# INTERFACE.net
KiCad netlist of a schematic drawn in Altium Designer
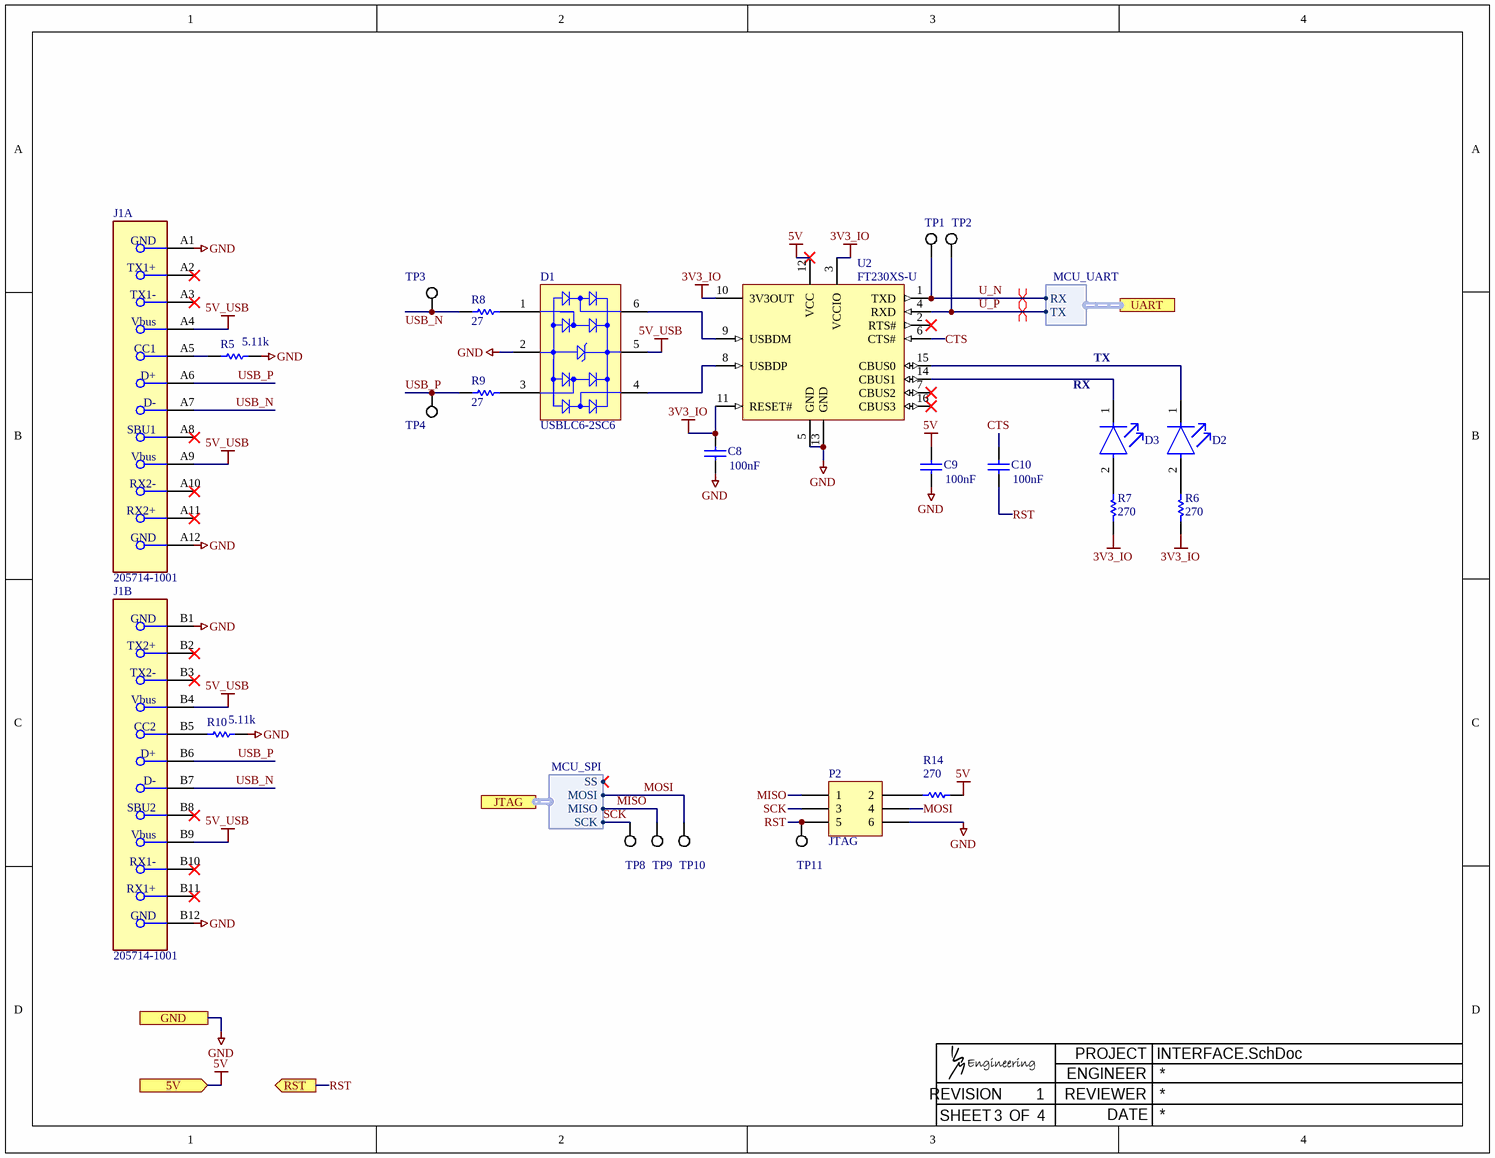
[diagram p0: INTERFACE.SchDoc]

(export (version "E")
  (design (tool "Eeschema 10.0.6"))
  (components
    (comp (ref "C8")
      (value "100nF")
      (footprint "CAPC1005X56X25ML10T15")
      (fields
        (field (name "MANUFACTURER") "AVX Interconnect / Elco")
        (field (name "PART NUMBER") "0402YG104ZAT2A")
      )
      (libsource (lib "Altium Content Vault") (part "CAP"))
    )
    (comp (ref "C9")
      (value "100nF")
      (footprint "CAPC1005X56X25ML10T15")
      (fields
        (field (name "MANUFACTURER") "AVX Interconnect / Elco")
        (field (name "PART NUMBER") "0402YG104ZAT2A")
      )
      (libsource (lib "Altium Content Vault") (part "CAP"))
    )
    (comp (ref "C10")
      (value "100nF")
      (footprint "CAPC1005X56X25ML10T15")
      (fields
        (field (name "MANUFACTURER") "AVX Interconnect / Elco")
        (field (name "PART NUMBER") "0402YG104ZAT2A")
      )
      (libsource (lib "Altium Content Vault") (part "CAP"))
    )
    (comp (ref "D1")
      (value "USBLC6-2SC6")
      (footprint "STM-SOT23-6L_V")
      (description "Very low capacitance ESD protection, 3.5 pF, -40 to 125 degC, 6-Pin SOT23, RoHS, Tape and Reel")
      (fields (field (name "MANUFACTURER") "STMicroelectronics"))
      (libsource (lib "Altium Content Vault") (part "STM-USB_DVI_HDMIULC6-4SC6X-SOT23-6L"))
    )
    (comp (ref "D2")
      (value "LTST-C190KGKT")
      (footprint "FP-LTST-C190KGKT-MFG")
      (description "LED GREEN CLEAR CHIP SMD")
      (libsource (lib "Altium Content Vault") (part "8706943c75ba83719d021d2fdc84c58"))
    )
    (comp (ref "D3")
      (value "LTST-C190KGKT")
      (footprint "FP-LTST-C190KGKT-MFG")
      (description "LED GREEN CLEAR CHIP SMD")
      (libsource (lib "Altium Content Vault") (part "8706943c75ba83719d021d2fdc84c58"))
    )
    (comp (ref "J1")
      (value "205714-1001")
      (footprint "FP-205714-1001-MFG")
      (description "USB TYPE C WITH SCREW HOLE  GM")
      (libsource (lib "Altium Content Vault") (part "1a8b11fb010c6447a7219bce639d1f1"))
    )
    (comp (ref "P2")
      (value "MHDR2X3")
      (footprint "MHDR2X3")
      (description "Header, 3-Pin, Dual row")
      (fields (field (name "PUBLISHER") "Altium Limited"))
      (libsource (lib "Miscellaneous Connectors") (part "MHDR2X3"))
    )
    (comp (ref "R5")
      (value "5.11k")
      (footprint "RESC1005X40X25NL05T05")
      (fields (field (name "MANUFACTURER") "Panasonic") (field (name "PART NUMBER") "ERJ-2RKF5111X"))
      (libsource (lib "Altium Content Vault") (part "RES"))
    )
    (comp (ref "R6")
      (value "270")
      (footprint "RESC1005X40X25NL05T05")
      (fields (field (name "PART NUMBER") "ERJ2RKF2700X") (field (name "MANUFACTURER") "Panasonic"))
      (libsource (lib "Altium Content Vault") (part "RES"))
    )
    (comp (ref "R7")
      (value "270")
      (footprint "RESC1005X40X25NL05T05")
      (fields (field (name "PART NUMBER") "ERJ2RKF2700X") (field (name "MANUFACTURER") "Panasonic"))
      (libsource (lib "Altium Content Vault") (part "RES"))
    )
    (comp (ref "R8")
      (value "27")
      (footprint "RESC1005X40X25LL10T10")
      (fields (field (name "PART NUMBER") "RK73B1ETTP270J") (field (name "MANUFACTURER") "KOA Speer"))
      (libsource (lib "Altium Content Vault") (part "RES"))
    )
    (comp (ref "R9")
      (value "27")
      (footprint "RESC1005X40X25LL10T10")
      (fields (field (name "PART NUMBER") "RK73B1ETTP270J") (field (name "MANUFACTURER") "KOA Speer"))
      (libsource (lib "Altium Content Vault") (part "RES"))
    )
    (comp (ref "R10")
      (value "5.11k")
      (footprint "RESC1005X40X25NL05T05")
      (fields (field (name "MANUFACTURER") "Panasonic") (field (name "PART NUMBER") "ERJ-2RKF5111X"))
      (libsource (lib "Altium Content Vault") (part "RES"))
    )
    (comp (ref "R14")
      (value "270")
      (footprint "RESC1005X40X25NL05T05")
      (fields (field (name "PART NUMBER") "ERJ2RKF2700X") (field (name "MANUFACTURER") "Panasonic"))
      (libsource (lib "Altium Content Vault") (part "RES"))
    )
    (comp (ref "TP1")
      (value "5019")
      (footprint "KSTN-5019_V")
      (description "Test Point, 1 Position SMD, RoHS, Tape and Reel")
      (libsource (lib "Altium Content Vault") (part "TESTPOINT_WHITE"))
    )
    (comp (ref "TP2")
      (value "5019")
      (footprint "KSTN-5019_V")
      (description "Test Point, 1 Position SMD, RoHS, Tape and Reel")
      (libsource (lib "Altium Content Vault") (part "TESTPOINT_WHITE"))
    )
    (comp (ref "TP3")
      (value "5019")
      (footprint "KSTN-5019_V")
      (description "Test Point, 1 Position SMD, RoHS, Tape and Reel")
      (libsource (lib "Altium Content Vault") (part "TESTPOINT_WHITE"))
    )
    (comp (ref "TP4")
      (value "5019")
      (footprint "KSTN-5019_V")
      (description "Test Point, 1 Position SMD, RoHS, Tape and Reel")
      (libsource (lib "Altium Content Vault") (part "TESTPOINT_WHITE"))
    )
    (comp (ref "TP8")
      (value "5019")
      (footprint "KSTN-5019_V")
      (description "Test Point, 1 Position SMD, RoHS, Tape and Reel")
      (libsource (lib "Altium Content Vault") (part "TESTPOINT_WHITE"))
    )
    (comp (ref "TP9")
      (value "5019")
      (footprint "KSTN-5019_V")
      (description "Test Point, 1 Position SMD, RoHS, Tape and Reel")
      (libsource (lib "Altium Content Vault") (part "TESTPOINT_WHITE"))
    )
    (comp (ref "TP10")
      (value "5019")
      (footprint "KSTN-5019_V")
      (description "Test Point, 1 Position SMD, RoHS, Tape and Reel")
      (libsource (lib "Altium Content Vault") (part "TESTPOINT_WHITE"))
    )
    (comp (ref "TP11")
      (value "5019")
      (footprint "KSTN-5019_V")
      (description "Test Point, 1 Position SMD, RoHS, Tape and Reel")
      (libsource (lib "Altium Content Vault") (part "TESTPOINT_WHITE"))
    )
    (comp (ref "U2")
      (value "FT230XS-U")
      (footprint "SSOP-16_N")
      (fields (field (name "MANUFACTURER") "FTDI"))
      (libsource (lib "Altium Content Vault") (part "COM-USB-FT230XS-IL16"))
    )
  )
  (nets
    (net (code "3") (name "/CTS") (class "Default")
      (node (ref "C10") (pin "2") (pinfunction "2_2") (pintype "passive"))
      (node (ref "U2") (pin "6") (pinfunction "CTS#_6") (pintype "input"))
    )
    (net (code "4") (name "/MISO") (class "Default")
      (node (ref "P2") (pin "1") (pinfunction "1_1") (pintype "passive"))
      (node (ref "TP9") (pin "1") (pinfunction "1_1") (pintype "passive"))
    )
    (net (code "5") (name "/MOSI") (class "Default")
      (node (ref "P2") (pin "4") (pinfunction "4_4") (pintype "passive"))
      (node (ref "TP10") (pin "1") (pinfunction "1_1") (pintype "passive"))
    )
    (net (code "6") (name "/RST") (class "Default")
      (node (ref "C10") (pin "1") (pinfunction "1_1") (pintype "passive"))
      (node (ref "P2") (pin "5") (pinfunction "5_5") (pintype "passive"))
      (node (ref "TP11") (pin "1") (pinfunction "1_1") (pintype "passive"))
    )
    (net (code "7") (name "/SCK") (class "Default")
      (node (ref "P2") (pin "3") (pinfunction "3_3") (pintype "passive"))
      (node (ref "TP8") (pin "1") (pinfunction "1_1") (pintype "passive"))
    )
    (net (code "8") (name "/USB_N") (class "Default")
      (node (ref "J1") (pin "A7") (pinfunction "D-_A7") (pintype "passive"))
      (node (ref "J1") (pin "B7") (pinfunction "D-_B7") (pintype "passive"))
      (node (ref "R8") (pin "1") (pinfunction "1_1") (pintype "passive"))
      (node (ref "TP3") (pin "1") (pinfunction "1_1") (pintype "passive"))
    )
    (net (code "9") (name "/USB_P") (class "Default")
      (node (ref "J1") (pin "A6") (pinfunction "D+_A6") (pintype "passive"))
      (node (ref "J1") (pin "B6") (pinfunction "D+_B6") (pintype "passive"))
      (node (ref "R9") (pin "1") (pinfunction "1_1") (pintype "passive"))
      (node (ref "TP4") (pin "1") (pinfunction "1_1") (pintype "passive"))
    )
    (net (code "10") (name "/U_N") (class "Default")
      (node (ref "TP1") (pin "1") (pinfunction "1_1") (pintype "passive"))
      (node (ref "U2") (pin "1") (pinfunction "TXD_1") (pintype "output"))
    )
    (net (code "11") (name "/U_P") (class "Default")
      (node (ref "TP2") (pin "1") (pinfunction "1_1") (pintype "passive"))
      (node (ref "U2") (pin "4") (pinfunction "RXD_4") (pintype "input"))
    )
    (net (code "14") (name "3V3_IO") (class "Default")
      (node (ref "C8") (pin "2") (pinfunction "2_2") (pintype "passive"))
      (node (ref "R6") (pin "2") (pinfunction "2_2") (pintype "passive"))
      (node (ref "R7") (pin "2") (pinfunction "2_2") (pintype "passive"))
      (node (ref "U2") (pin "10") (pinfunction "3V3OUT_10") (pintype "power_in"))
      (node (ref "U2") (pin "11") (pinfunction "RESET#_11") (pintype "input"))
      (node (ref "U2") (pin "3") (pinfunction "VCCIO_3") (pintype "power_in"))
    )
    (net (code "15") (name "5V") (class "Default")
      (node (ref "C9") (pin "2") (pinfunction "2_2") (pintype "passive"))
      (node (ref "R14") (pin "1") (pinfunction "1_1") (pintype "passive"))
      (node (ref "U2") (pin "12") (pinfunction "VCC_12") (pintype "power_in"))
    )
    (net (code "16") (name "5V_USB") (class "Default")
      (node (ref "D1") (pin "5") (pinfunction "VBUS_5") (pintype "passive"))
      (node (ref "J1") (pin "A4") (pinfunction "Vbus_A4") (pintype "passive"))
      (node (ref "J1") (pin "A9") (pinfunction "Vbus_A9") (pintype "passive"))
      (node (ref "J1") (pin "B4") (pinfunction "Vbus_B4") (pintype "passive"))
      (node (ref "J1") (pin "B9") (pinfunction "Vbus_B9") (pintype "passive"))
    )
    (net (code "17") (name "GND") (class "Default")
      (node (ref "C8") (pin "1") (pinfunction "1_1") (pintype "passive"))
      (node (ref "C9") (pin "1") (pinfunction "1_1") (pintype "passive"))
      (node (ref "D1") (pin "2") (pinfunction "GND_2") (pintype "passive"))
      (node (ref "J1") (pin "A1") (pinfunction "GND_A1") (pintype "passive"))
      (node (ref "J1") (pin "A12") (pinfunction "GND_A12") (pintype "passive"))
      (node (ref "J1") (pin "B1") (pinfunction "GND_B1") (pintype "passive"))
      (node (ref "J1") (pin "B12") (pinfunction "GND_B12") (pintype "passive"))
      (node (ref "P2") (pin "6") (pinfunction "6_6") (pintype "passive"))
      (node (ref "R10") (pin "1") (pinfunction "1_1") (pintype "passive"))
      (node (ref "R5") (pin "1") (pinfunction "1_1") (pintype "passive"))
      (node (ref "U2") (pin "13") (pinfunction "GND_13") (pintype "power_in"))
      (node (ref "U2") (pin "5") (pinfunction "GND_5") (pintype "power_in"))
    )
    (net (code "18") (name "Net-(D1-I{slash}O_1)") (class "Default")
      (node (ref "D1") (pin "1") (pinfunction "I/O_1_1") (pintype "passive"))
      (node (ref "R8") (pin "2") (pinfunction "2_2") (pintype "passive"))
    )
    (net (code "19") (name "Net-(D1-I{slash}O_2)") (class "Default")
      (node (ref "D1") (pin "3") (pinfunction "I/O_2_3") (pintype "passive"))
      (node (ref "R9") (pin "2") (pinfunction "2_2") (pintype "passive"))
    )
    (net (code "20") (name "Net-(D1-I{slash}O_3)") (class "Default")
      (node (ref "D1") (pin "4") (pinfunction "I/O_3_4") (pintype "passive"))
      (node (ref "U2") (pin "8") (pinfunction "USBDP_8") (pintype "input"))
    )
    (net (code "21") (name "Net-(D1-I{slash}O_4)") (class "Default")
      (node (ref "D1") (pin "6") (pinfunction "I/O_4_6") (pintype "passive"))
      (node (ref "U2") (pin "9") (pinfunction "USBDM_9") (pintype "input"))
    )
    (net (code "22") (name "Net-(D2-A)") (class "Default")
      (node (ref "D2") (pin "2") (pinfunction "A_2") (pintype "passive"))
      (node (ref "R6") (pin "1") (pinfunction "1_1") (pintype "passive"))
    )
    (net (code "23") (name "Net-(D2-C)") (class "Default")
      (node (ref "D2") (pin "1") (pinfunction "C_1") (pintype "passive"))
      (node (ref "U2") (pin "15") (pinfunction "CBUS0_15") (pintype "bidirectional"))
    )
    (net (code "24") (name "Net-(D3-A)") (class "Default")
      (node (ref "D3") (pin "2") (pinfunction "A_2") (pintype "passive"))
      (node (ref "R7") (pin "1") (pinfunction "1_1") (pintype "passive"))
    )
    (net (code "25") (name "Net-(D3-C)") (class "Default")
      (node (ref "D3") (pin "1") (pinfunction "C_1") (pintype "passive"))
      (node (ref "U2") (pin "14") (pinfunction "CBUS1_14") (pintype "bidirectional"))
    )
    (net (code "26") (name "Net-(J1A-CC1)") (class "Default")
      (node (ref "J1") (pin "A5") (pinfunction "CC1_A5") (pintype "passive"))
      (node (ref "R5") (pin "2") (pinfunction "2_2") (pintype "passive"))
    )
    (net (code "27") (name "Net-(J1B-CC2)") (class "Default")
      (node (ref "J1") (pin "B5") (pinfunction "CC2_B5") (pintype "passive"))
      (node (ref "R10") (pin "2") (pinfunction "2_2") (pintype "passive"))
    )
    (net (code "28") (name "Net-(P2-Pad2)") (class "Default")
      (node (ref "P2") (pin "2") (pinfunction "2_2") (pintype "passive"))
      (node (ref "R14") (pin "2") (pinfunction "2_2") (pintype "passive"))
    )
    (net (code "29") (name "unconnected-(J1A-RX2+-PadA11)") (class "Default")
      (node (ref "J1") (pin "A11") (pinfunction "RX2+_A11") (pintype "passive+no_connect"))
    )
    (net (code "30") (name "unconnected-(J1A-RX2--PadA10)") (class "Default")
      (node (ref "J1") (pin "A10") (pinfunction "RX2-_A10") (pintype "passive+no_connect"))
    )
    (net (code "31") (name "unconnected-(J1A-SBU1-PadA8)") (class "Default")
      (node (ref "J1") (pin "A8") (pinfunction "SBU1_A8") (pintype "passive+no_connect"))
    )
    (net (code "32") (name "unconnected-(J1A-TX1+-PadA2)") (class "Default")
      (node (ref "J1") (pin "A2") (pinfunction "TX1+_A2") (pintype "passive+no_connect"))
    )
    (net (code "33") (name "unconnected-(J1A-TX1--PadA3)") (class "Default")
      (node (ref "J1") (pin "A3") (pinfunction "TX1-_A3") (pintype "passive+no_connect"))
    )
    (net (code "34") (name "unconnected-(J1B-RX1+-PadB11)") (class "Default")
      (node (ref "J1") (pin "B11") (pinfunction "RX1+_B11") (pintype "passive+no_connect"))
    )
    (net (code "35") (name "unconnected-(J1B-RX1--PadB10)") (class "Default")
      (node (ref "J1") (pin "B10") (pinfunction "RX1-_B10") (pintype "passive+no_connect"))
    )
    (net (code "36") (name "unconnected-(J1B-SBU2-PadB8)") (class "Default")
      (node (ref "J1") (pin "B8") (pinfunction "SBU2_B8") (pintype "passive+no_connect"))
    )
    (net (code "37") (name "unconnected-(J1B-TX2+-PadB2)") (class "Default")
      (node (ref "J1") (pin "B2") (pinfunction "TX2+_B2") (pintype "passive+no_connect"))
    )
    (net (code "38") (name "unconnected-(J1B-TX2--PadB3)") (class "Default")
      (node (ref "J1") (pin "B3") (pinfunction "TX2-_B3") (pintype "passive+no_connect"))
    )
    (net (code "39") (name "unconnected-(U2-CBUS2-Pad7)") (class "Default")
      (node (ref "U2") (pin "7") (pinfunction "CBUS2_7") (pintype "bidirectional+no_connect"))
    )
    (net (code "40") (name "unconnected-(U2-CBUS3-Pad16)") (class "Default")
      (node (ref "U2") (pin "16") (pinfunction "CBUS3_16") (pintype "bidirectional+no_connect"))
    )
    (net (code "41") (name "unconnected-(U2-RTS#-Pad2)") (class "Default")
      (node (ref "U2") (pin "2") (pinfunction "RTS#_2") (pintype "output+no_connect"))
    )
  )
)
